# VUE_PIC32_v1_0_CAN.net
KiCad netlist of a schematic drawn in Altium Designer
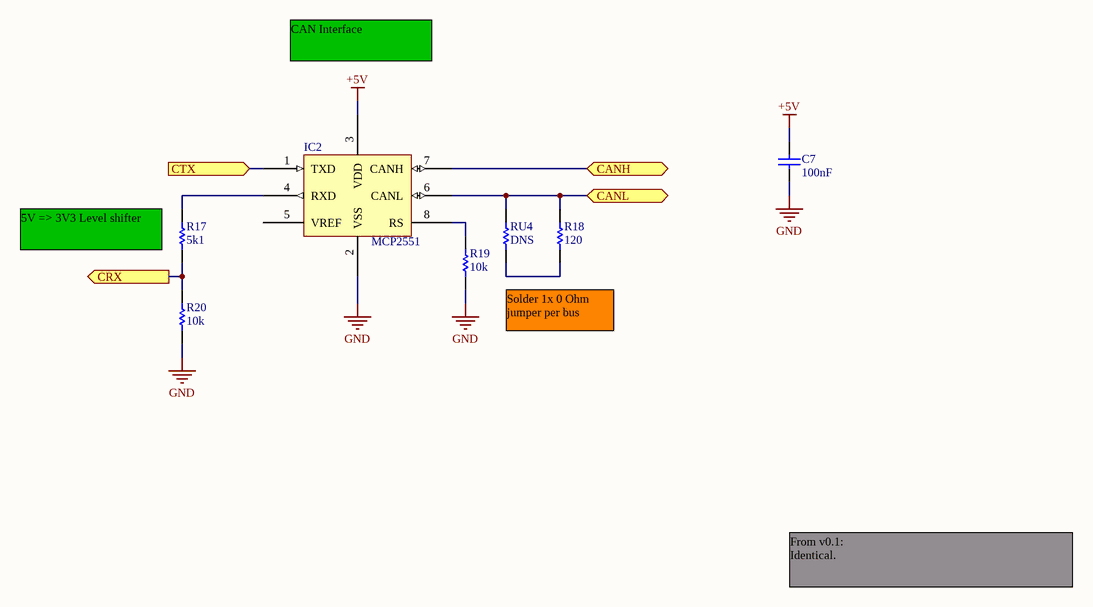
[diagram p0: VUE_PIC32_v1_0_CAN.SchDoc]

(export (version "E")
  (design (tool "Eeschema 10.0.6"))
  (components
    (comp (ref "C7")
      (value "100nF")
      (footprint "0402C")
      (description "CAP CER 0.1UF 25V Y5V 0402")
      (fields (field (name "MFG") "TDK") (field (name "MFGPARTNUMBER") "C1005Y5V1E104Z"))
      (libsource (lib "JFD_Cap") (part "CAP_TDK_C_0402_100nF_25V"))
    )
    (comp (ref "IC2")
      (value "MCP2551")
      (footprint "SOIC-8")
      (description "IC TRANSCEIVER CAN HI-SPD 8-SOIC")
      (fields (field (name "MFG") "Microchip Technology") (field (name "MFGPARTNUMBER") "MCP2551-I/SN"))
      (libsource (lib "JFD_IC") (part "IC_MICROCHIP_MCP2551_CAN_SOIC8"))
    )
    (comp (ref "R17")
      (value "5k1")
      (footprint "0402")
      (description "RES 5.10K OHM 1/16W 1% 0402 SMD")
      (fields (field (name "MFG") "Yageo") (field (name "MFGPARTNUMBER") "RC0402FR-075K1L"))
      (libsource (lib "JFD_Res") (part "RES_YAGEO_0402_5K1_1PCT"))
    )
    (comp (ref "R18")
      (value "120")
      (footprint "0402")
      (description "RES 120 OHM 1/16W 1% 0402 SMD")
      (fields (field (name "MFG") "Yageo") (field (name "MFGPARTNUMBER") "RC0402FR-07120RL"))
      (libsource (lib "JFD_Res") (part "RES_YAGEO_0402_120_1PCT"))
    )
    (comp (ref "R19")
      (value "10k")
      (footprint "0402")
      (description "RES 10.0K OHM 1/16W 1% 0402 SMD")
      (fields (field (name "MFG") "Yageo") (field (name "MFGPARTNUMBER") "RC0402FR-0710KL"))
      (libsource (lib "JFD_Res") (part "RES_YAGEO_0402_10K_1PCT"))
    )
    (comp (ref "R20")
      (value "10k")
      (footprint "0402")
      (description "RES 10.0K OHM 1/16W 1% 0402 SMD")
      (fields (field (name "MFG") "Yageo") (field (name "MFGPARTNUMBER") "RC0402FR-0710KL"))
      (libsource (lib "JFD_Res") (part "RES_YAGEO_0402_10K_1PCT"))
    )
    (comp (ref "RU4")
      (value "DNS")
      (footprint "0603")
      (description "Optional jumper - Do Not Solder")
      (fields (field (name "MFG") "NULL"))
      (libsource (lib "JFD_Res") (part "RES_DO_NOT_SOLDER_DNS_0603"))
    )
  )
  (nets
    (net (code "1") (name "+5V") (class "Default")
      (node (ref "C7") (pin "2") (pinfunction "2_2") (pintype "passive"))
      (node (ref "IC2") (pin "3") (pinfunction "VDD_3") (pintype "power_in"))
    )
    (net (code "2") (name "/CANH") (class "Default")
      (node (ref "IC2") (pin "7") (pinfunction "CANH_7") (pintype "bidirectional"))
    )
    (net (code "3") (name "/CANL") (class "Default")
      (node (ref "IC2") (pin "6") (pinfunction "CANL_6") (pintype "bidirectional"))
      (node (ref "R18") (pin "2") (pinfunction "2_2") (pintype "passive"))
      (node (ref "RU4") (pin "2") (pinfunction "2_2") (pintype "passive"))
    )
    (net (code "4") (name "/CRX") (class "Default")
      (node (ref "R17") (pin "1") (pinfunction "1_1") (pintype "passive"))
      (node (ref "R20") (pin "2") (pinfunction "2_2") (pintype "passive"))
    )
    (net (code "5") (name "/CTX") (class "Default")
      (node (ref "IC2") (pin "1") (pinfunction "TXD_1") (pintype "input"))
    )
    (net (code "6") (name "GND") (class "Default")
      (node (ref "C7") (pin "1") (pinfunction "1_1") (pintype "passive"))
      (node (ref "IC2") (pin "2") (pinfunction "VSS_2") (pintype "power_in"))
      (node (ref "R19") (pin "2") (pinfunction "2_2") (pintype "passive"))
      (node (ref "R20") (pin "1") (pinfunction "1_1") (pintype "passive"))
    )
    (net (code "7") (name "Net-(IC2-RS)") (class "Default")
      (node (ref "IC2") (pin "8") (pinfunction "RS_8") (pintype "passive"))
      (node (ref "R19") (pin "1") (pinfunction "1_1") (pintype "passive"))
    )
    (net (code "8") (name "Net-(IC2-RXD)") (class "Default")
      (node (ref "IC2") (pin "4") (pinfunction "RXD_4") (pintype "output"))
      (node (ref "R17") (pin "2") (pinfunction "2_2") (pintype "passive"))
    )
    (net (code "9") (name "Net-(R18-Pad1)") (class "Default")
      (node (ref "R18") (pin "1") (pinfunction "1_1") (pintype "passive"))
      (node (ref "RU4") (pin "1") (pinfunction "1_1") (pintype "passive"))
    )
    (net (code "10") (name "unconnected-(IC2-VREF-Pad5)") (class "Default")
      (node (ref "IC2") (pin "5") (pinfunction "VREF_5") (pintype "passive"))
    )
  )
)
